# filter_diff_shunt.net
KiCad netlist of a schematic drawn in Altium Designer
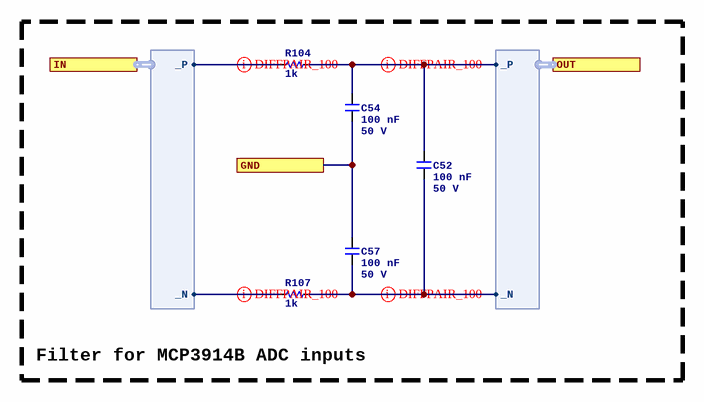
[diagram p0: filter_diff_shunt.SchDoc]

(export (version "E")
  (design (tool "Eeschema 10.0.6"))
  (components
    (comp (ref "C52")
      (value "CL05B104KB54PNC")
      (footprint "C0402")
      (fields
        (field (name "CAPACITANCE") "100 nF")
        (field (name "MANUFACTURER") "Samsung Electro-Mechanics")
        (field (name "VOLTAGE RATING") "50 V")
      )
      (libsource (lib "database") (part "__template_cap"))
    )
    (comp (ref "C54")
      (value "CL05B104KB54PNC")
      (footprint "C0402")
      (fields
        (field (name "CAPACITANCE") "100 nF")
        (field (name "MANUFACTURER") "Samsung Electro-Mechanics")
        (field (name "VOLTAGE RATING") "50 V")
      )
      (libsource (lib "database") (part "__template_cap"))
    )
    (comp (ref "C57")
      (value "CL05B104KB54PNC")
      (footprint "C0402")
      (fields
        (field (name "CAPACITANCE") "100 nF")
        (field (name "MANUFACTURER") "Samsung Electro-Mechanics")
        (field (name "VOLTAGE RATING") "50 V")
      )
      (libsource (lib "database") (part "__template_cap"))
    )
    (comp (ref "R104")
      (value "1k")
      (footprint "R0402")
      (fields
        (field (name "TOLERANCE") "1%")
        (field (name "MANUFACTURER PART NUMBER") "0402WGF1001TCE")
        (field (name "MANUFACTURER") "UNI-ROYAL(Uniroyal Elec)")
      )
      (libsource (lib "database") (part "__template_resistor"))
    )
    (comp (ref "R107")
      (value "1k")
      (footprint "R0402")
      (fields
        (field (name "TOLERANCE") "1%")
        (field (name "MANUFACTURER PART NUMBER") "0402WGF1001TCE")
        (field (name "MANUFACTURER") "UNI-ROYAL(Uniroyal Elec)")
      )
      (libsource (lib "database") (part "__template_resistor"))
    )
  )
  (nets
    (net (code "2") (name "/GND") (class "Default")
      (node (ref "C54") (pin "2") (pintype "passive"))
      (node (ref "C57") (pin "1") (pintype "passive"))
    )
    (net (code "4") (name "Net-(C52-Pad1)") (class "Default")
      (node (ref "C52") (pin "1") (pintype "passive"))
      (node (ref "C54") (pin "1") (pintype "passive"))
      (node (ref "R104") (pin "1") (pintype "passive"))
    )
    (net (code "5") (name "Net-(C52-Pad2)") (class "Default")
      (node (ref "C52") (pin "2") (pintype "passive"))
      (node (ref "C57") (pin "2") (pintype "passive"))
      (node (ref "R107") (pin "1") (pintype "passive"))
    )
    (net (code "6") (name "unconnected-(R104-Pad2)") (class "Default")
      (node (ref "R104") (pin "2") (pintype "passive"))
    )
    (net (code "7") (name "unconnected-(R107-Pad2)") (class "Default")
      (node (ref "R107") (pin "2") (pintype "passive"))
    )
  )
)
